# Power.net
KiCad netlist of a schematic drawn in Altium Designer
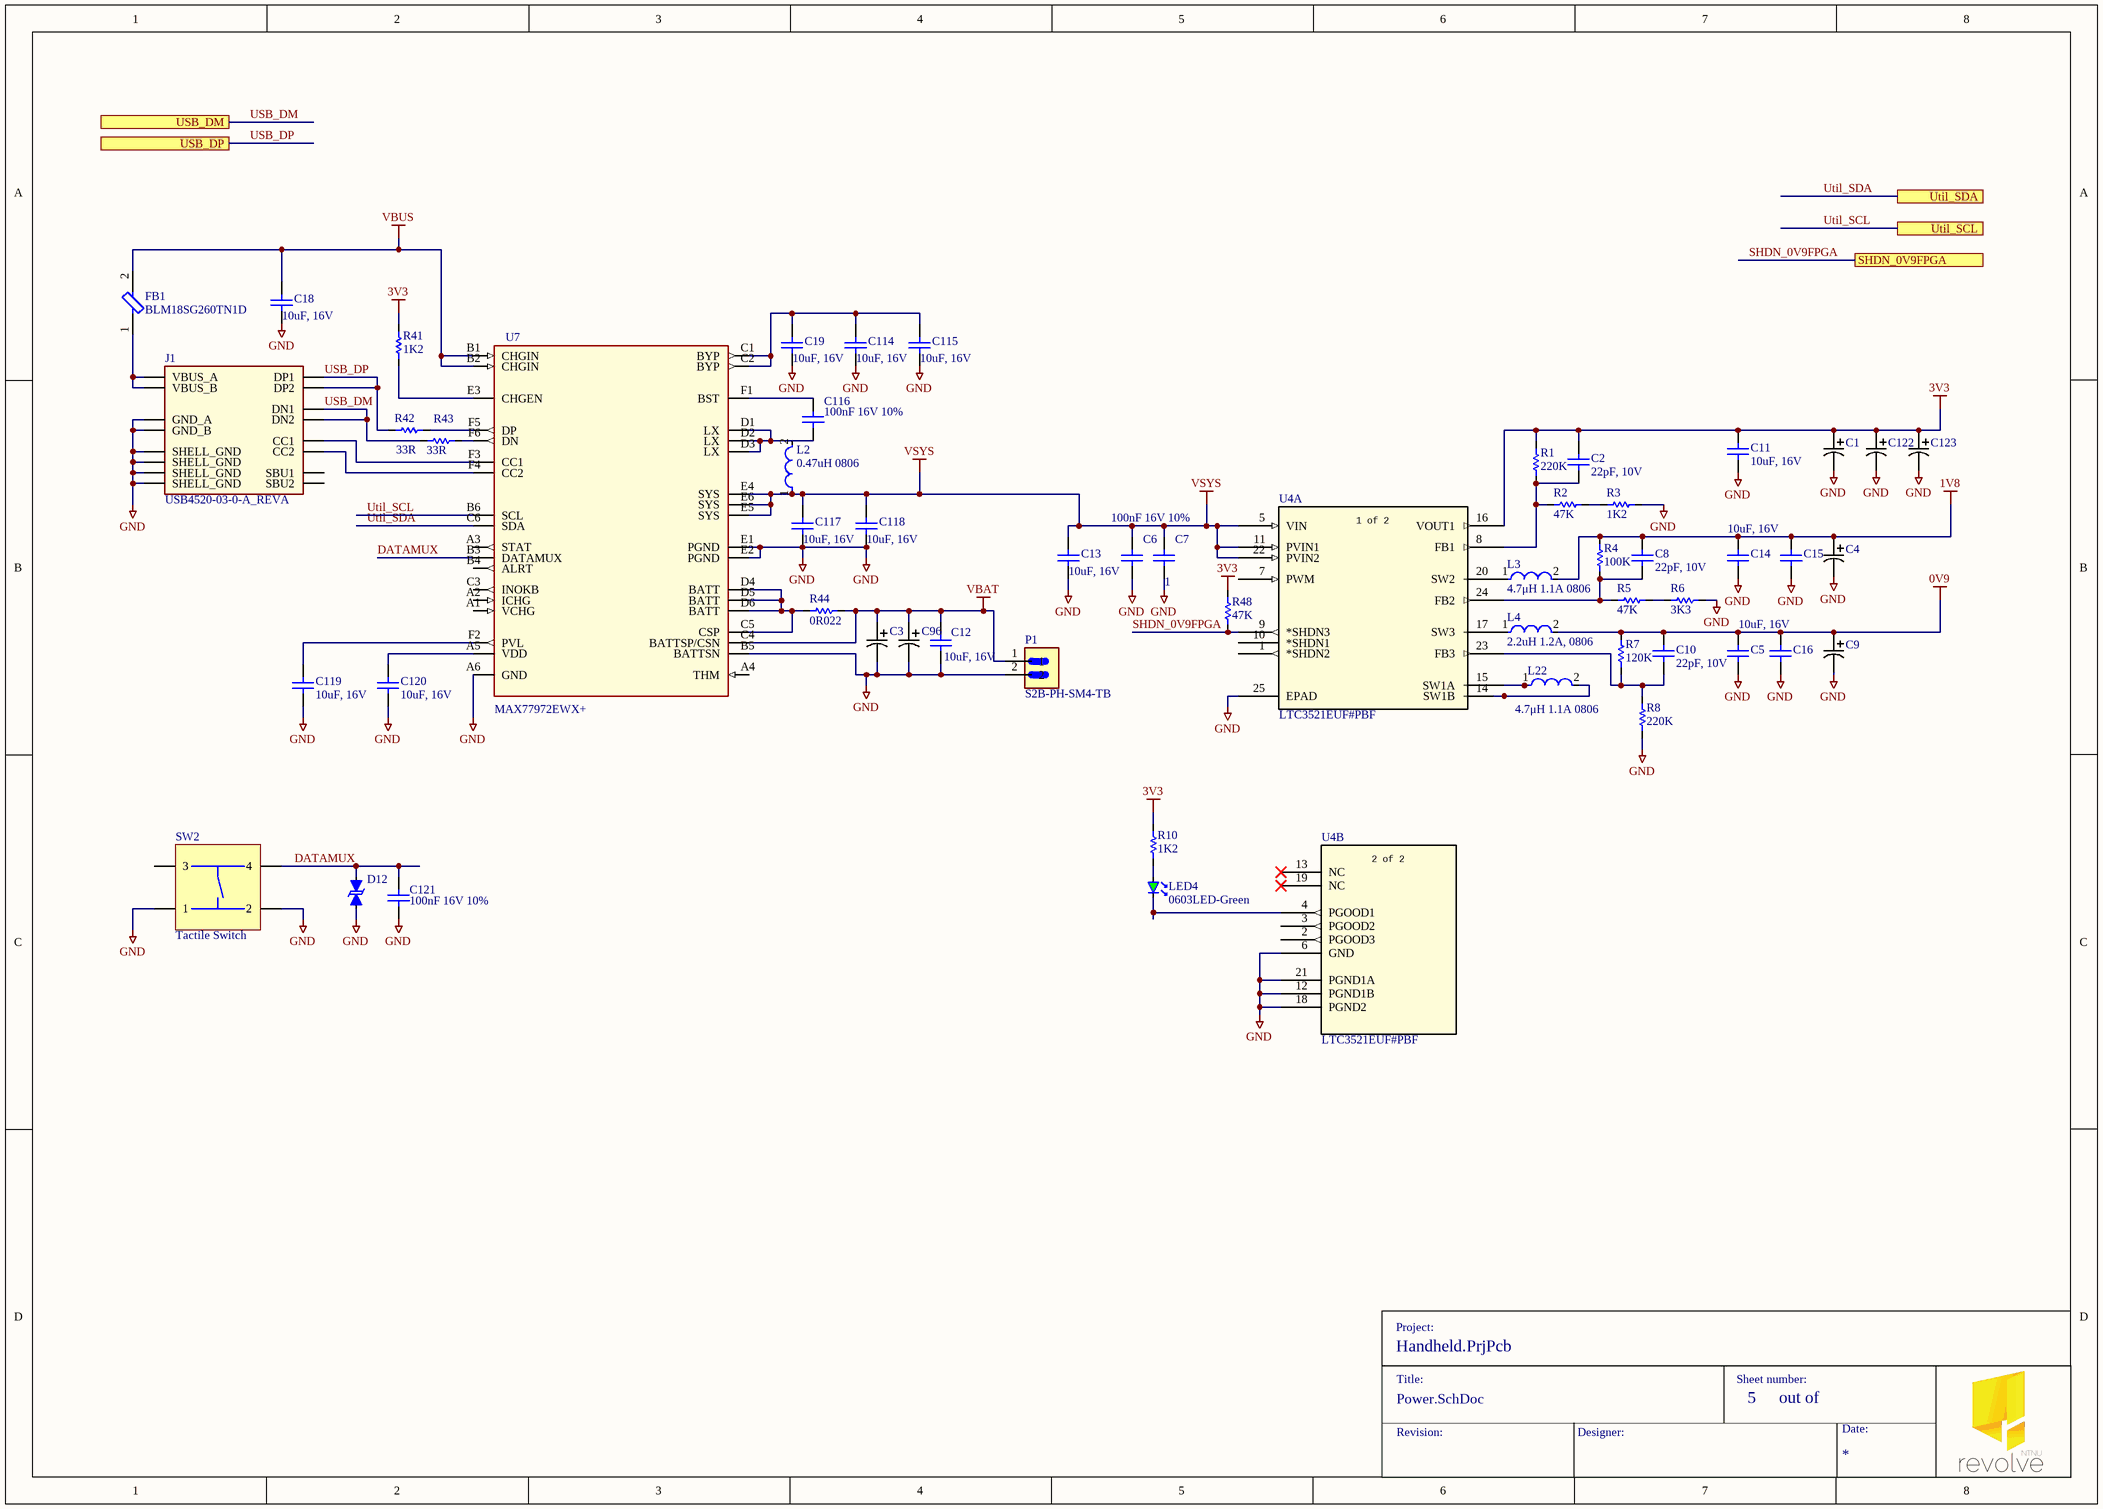
[diagram p0: Power.SchDoc]

(export (version "E")
  (design (tool "Eeschema 10.0.6"))
  (components
    (comp (ref "C1")
      (value "T529P476M006AAE150")
      (footprint "CAPMP2.1X1.25_1N_KEM")
      (fields (field (name "COPYRIGHT") "Copyright (C) 2025 Ultra Librarian. All rights reserved."))
      (libsource (lib "Handheld") (part "CAP-47uF-6.3V 0805"))
    )
    (comp (ref "C2")
      (value "22pF, 10V")
      (footprint "0603 Capacitor")
      (description "22pF, 10V, 1%, NP0, 0603")
      (libsource (lib "Revolve NTNU") (part "CAP"))
    )
    (comp (ref "C3")
      (value "T529P476M006AAE150")
      (footprint "CAPMP2.1X1.25_1N_KEM")
      (fields (field (name "COPYRIGHT") "Copyright (C) 2025 Ultra Librarian. All rights reserved."))
      (libsource (lib "Handheld") (part "CAP-47uF-6.3V 0805"))
    )
    (comp (ref "C4")
      (value "T529P476M006AAE150")
      (footprint "CAPMP2.1X1.25_1N_KEM")
      (fields (field (name "COPYRIGHT") "Copyright (C) 2025 Ultra Librarian. All rights reserved."))
      (libsource (lib "Handheld") (part "CAP-47uF-6.3V 0805"))
    )
    (comp (ref "C5")
      (value "10uF, 16V")
      (footprint "0603 Capacitor")
      (description "10uF, 16V, 20%, X5R, 0603")
      (libsource (lib "Revolve NTNU") (part "CAP"))
    )
    (comp (ref "C6")
      (value "100nF 16V 10%")
      (footprint "0402")
      (description "100nF 16V")
      (libsource (lib "Revolve NTNU") (part "CAP"))
    )
    (comp (ref "C7")
      (value "1")
      (footprint "0402")
      (description "100nF 16V")
      (libsource (lib "Revolve NTNU") (part "CAP"))
    )
    (comp (ref "C8")
      (value "22pF, 10V")
      (footprint "0603 Capacitor")
      (description "22pF, 10V, 1%, NP0, 0603")
      (libsource (lib "Revolve NTNU") (part "CAP"))
    )
    (comp (ref "C9")
      (value "T529P476M006AAE150")
      (footprint "CAPMP2.1X1.25_1N_KEM")
      (fields (field (name "COPYRIGHT") "Copyright (C) 2025 Ultra Librarian. All rights reserved."))
      (libsource (lib "Handheld") (part "CAP-47uF-6.3V 0805"))
    )
    (comp (ref "C10")
      (value "22pF, 10V")
      (footprint "0603 Capacitor")
      (description "22pF, 10V, 1%, NP0, 0603")
      (libsource (lib "Revolve NTNU") (part "CAP"))
    )
    (comp (ref "C11")
      (value "10uF, 16V")
      (footprint "0603 Capacitor")
      (description "10uF, 16V, 20%, X5R, 0603")
      (libsource (lib "Revolve NTNU") (part "CAP"))
    )
    (comp (ref "C12")
      (value "10uF, 16V")
      (footprint "0603 Capacitor")
      (description "10uF, 16V, 20%, X5R, 0603")
      (libsource (lib "Revolve NTNU") (part "CAP"))
    )
    (comp (ref "C13")
      (value "10uF, 16V")
      (footprint "0603 Capacitor")
      (description "10uF, 16V, 20%, X5R, 0603")
      (libsource (lib "Revolve NTNU") (part "CAP"))
    )
    (comp (ref "C14")
      (value "10uF, 16V")
      (footprint "0603 Capacitor")
      (description "10uF, 16V, 20%, X5R, 0603")
      (libsource (lib "Revolve NTNU") (part "CAP"))
    )
    (comp (ref "C15")
      (value "10uF, 16V")
      (footprint "0603 Capacitor")
      (description "10uF, 16V, 20%, X5R, 0603")
      (libsource (lib "Revolve NTNU") (part "CAP"))
    )
    (comp (ref "C16")
      (value "10uF, 16V")
      (footprint "0603 Capacitor")
      (description "10uF, 16V, 20%, X5R, 0603")
      (libsource (lib "Revolve NTNU") (part "CAP"))
    )
    (comp (ref "C18")
      (value "10uF, 16V")
      (footprint "0603 Capacitor")
      (description "10uF, 16V, 20%, X5R, 0603")
      (libsource (lib "Revolve NTNU") (part "CAP"))
    )
    (comp (ref "C19")
      (value "10uF, 16V")
      (footprint "0603 Capacitor")
      (description "10uF, 16V, 20%, X5R, 0603")
      (libsource (lib "Revolve NTNU") (part "CAP"))
    )
    (comp (ref "C96")
      (value "T529P476M006AAE150")
      (footprint "CAPMP2.1X1.25_1N_KEM")
      (fields (field (name "COPYRIGHT") "Copyright (C) 2025 Ultra Librarian. All rights reserved."))
      (libsource (lib "Handheld") (part "CAP-47uF-6.3V 0805"))
    )
    (comp (ref "C114")
      (value "10uF, 16V")
      (footprint "0603 Capacitor")
      (description "10uF, 16V, 20%, X5R, 0603")
      (libsource (lib "Revolve NTNU") (part "CAP"))
    )
    (comp (ref "C115")
      (value "10uF, 16V")
      (footprint "0603 Capacitor")
      (description "10uF, 16V, 20%, X5R, 0603")
      (libsource (lib "Revolve NTNU") (part "CAP"))
    )
    (comp (ref "C116")
      (value "100nF 16V 10%")
      (footprint "0402")
      (description "100nF 16V")
      (libsource (lib "Revolve NTNU") (part "CAP"))
    )
    (comp (ref "C117")
      (value "10uF, 16V")
      (footprint "0603 Capacitor")
      (description "10uF, 16V, 20%, X5R, 0603")
      (libsource (lib "Revolve NTNU") (part "CAP"))
    )
    (comp (ref "C118")
      (value "10uF, 16V")
      (footprint "0603 Capacitor")
      (description "10uF, 16V, 20%, X5R, 0603")
      (libsource (lib "Revolve NTNU") (part "CAP"))
    )
    (comp (ref "C119")
      (value "10uF, 16V")
      (footprint "0603 Capacitor")
      (description "10uF, 16V, 20%, X5R, 0603")
      (libsource (lib "Revolve NTNU") (part "CAP"))
    )
    (comp (ref "C120")
      (value "10uF, 16V")
      (footprint "0603 Capacitor")
      (description "10uF, 16V, 20%, X5R, 0603")
      (libsource (lib "Revolve NTNU") (part "CAP"))
    )
    (comp (ref "C121")
      (value "100nF 16V 10%")
      (footprint "0402")
      (description "100nF 16V")
      (libsource (lib "Revolve NTNU") (part "CAP"))
    )
    (comp (ref "C122")
      (value "T529P476M006AAE150")
      (footprint "CAPMP2.1X1.25_1N_KEM")
      (fields (field (name "COPYRIGHT") "Copyright (C) 2025 Ultra Librarian. All rights reserved."))
      (libsource (lib "Handheld") (part "CAP-47uF-6.3V 0805"))
    )
    (comp (ref "C123")
      (value "T529P476M006AAE150")
      (footprint "CAPMP2.1X1.25_1N_KEM")
      (fields (field (name "COPYRIGHT") "Copyright (C) 2025 Ultra Librarian. All rights reserved."))
      (libsource (lib "Handheld") (part "CAP-47uF-6.3V 0805"))
    )
    (comp (ref "D12")
      (value "DESD3V3E1BL-7B")
      (footprint "CR_X1-DFN1006-2_DIO-M")
      (description "TVS DIODE 3.3V, DFN1006-2, 13pF @ 1MHz")
      (fields (field (name "COPYRIGHT") "Copyright (C) 2025 Ultra Librarian. All rights reserved."))
      (libsource (lib "Handheld") (part "DESD3V3E1BL-7B"))
    )
    (comp (ref "FB1")
      (value "BLM18SG260TN1D")
      (footprint "FP-BLM18-0_15-t0_5-d3_3-IPC_B")
      (description "Ferrite Bead, 26 Ohm @ 100 MHz, 6A, 7mOhm")
      (libsource (lib "Revolve NTNU") (part "5f30dd21d616792df468990f7003faa"))
    )
    (comp (ref "J1")
      (value "USB4520-03-0-A_REVA")
      (footprint "GCT_USB4520-03-0-A_REVA")
      (description "USB Type C Receptacle for USB 2.0, SMT Type Mid Mount, 2.0mm Offset")
      (fields (field (name "MF") "Global Connector Technology") (field (name "MP") "USB4520-03-0-A"))
      (libsource (lib "Handheld") (part "USB-C"))
    )
    (comp (ref "L2")
      (value "0.47uH 0806")
      (footprint "FP-LQM2MPN_G0-IPC_B")
      (fields (field (name "TOLERANCE") "30%"))
      (libsource (lib "Handheld") (part "Inductor SMD 0.47uH"))
    )
    (comp (ref "L3")
      (value "4.7μH 1.1A 0806")
      (footprint "FP-LQM2MPN_G0-IPC_B")
      (description "Multilayer Type Inductor for Power Lines, 0806 (2016), 4.7μH, 30%, 0.175Ω, 1.1A, LQM2MPN4R7NG0L")
      (fields (field (name "TOLERANCE") "30%"))
      (libsource (lib "Handheld") (part "Inductor SMD 4.7uH 1.1A"))
    )
    (comp (ref "L4")
      (value "2.2uH 1.2A, 0806")
      (footprint "FP-LQM2MPN_G0-IPC_B")
      (description "Multilayer Type Inductor for Power Lines, 0806 (2016), 4.7μH, 30%, 0.175Ω, 1.1A, LQM2MPN2R2NG0L")
      (fields (field (name "TOLERANCE") "30%"))
      (libsource (lib "Handheld") (part "Inductor SMD 2.2uH 1.2A"))
    )
    (comp (ref "L22")
      (value "4.7μH 1.1A 0806")
      (footprint "FP-LQM2MPN_G0-IPC_B")
      (description "Multilayer Type Inductor for Power Lines, 0806 (2016), 4.7μH, 30%, 0.175Ω, 1.1A, LQM2MPN4R7NG0L")
      (fields (field (name "TOLERANCE") "30%"))
      (libsource (lib "Handheld") (part "Inductor SMD 4.7uH 1.1A"))
    )
    (comp (ref "LED4")
      (value "0603LED-Green")
      (footprint "LED-0603-RED")
      (description "SMD LED 0603, Green")
      (libsource (lib "Revolve NTNU") (part "LED"))
    )
    (comp (ref "P1")
      (value "S2B-PH-SM4-TB")
      (footprint "JST_S2B-PH-SM4-TB")
      (description "Connector Header Surface Mount, Right Angle 2 position 0.079 (2.00mm)")
      (fields (field (name "MF") "JST Sales"))
      (libsource (lib "Eirik Silnes") (part "S2B-PH-SM4-TB"))
    )
    (comp (ref "R1")
      (value "220K")
      (footprint "0603 Resistor")
      (description "220K, 1%, 1/10W, 0603")
      (libsource (lib "Revolve NTNU") (part "Resistor"))
    )
    (comp (ref "R2")
      (value "47K")
      (footprint "0603 Resistor")
      (description "47K, 1%, 1/10W, 0603")
      (libsource (lib "Revolve NTNU") (part "Resistor"))
    )
    (comp (ref "R3")
      (value "1K2")
      (footprint "0603 Resistor")
      (description "1K2, 5%, 1/10W, 0603")
      (libsource (lib "Revolve NTNU") (part "Resistor"))
    )
    (comp (ref "R4")
      (value "100K")
      (footprint "0603 Resistor")
      (description "100K, 1%, 1/10W, 0603")
      (fields (field (name "TOLERANCE") "1%") (field (name "MANUFACTURER PART NUMBER") "ERJ-3EKF1003V"))
      (libsource (lib "Revolve NTNU") (part "Resistor"))
    )
    (comp (ref "R5")
      (value "47K")
      (footprint "0603 Resistor")
      (description "47K, 1%, 1/10W, 0603")
      (libsource (lib "Revolve NTNU") (part "Resistor"))
    )
    (comp (ref "R6")
      (value "3K3")
      (footprint "0603 Resistor")
      (description "3K3, 5%, 1/10W, 0603")
      (libsource (lib "Revolve NTNU") (part "Resistor"))
    )
    (comp (ref "R7")
      (value "120K")
      (footprint "0603 Resistor")
      (description "120K, 0.1%, 1/10W, 0603")
      (libsource (lib "Revolve NTNU") (part "Resistor"))
    )
    (comp (ref "R8")
      (value "220K")
      (footprint "0603 Resistor")
      (description "220K, 1%, 1/10W, 0603")
      (libsource (lib "Revolve NTNU") (part "Resistor"))
    )
    (comp (ref "R10")
      (value "1K2")
      (footprint "0603 Resistor")
      (description "1K2, 5%, 1/10W, 0603")
      (libsource (lib "Revolve NTNU") (part "Resistor"))
    )
    (comp (ref "R41")
      (value "1K2")
      (footprint "0603 Resistor")
      (description "1K2, 5%, 1/10W, 0603")
      (libsource (lib "Revolve NTNU") (part "Resistor"))
    )
    (comp (ref "R42")
      (value "33R")
      (footprint "0603 Resistor")
      (description "33R, 1%, 1/10W, 0603")
      (fields (field (name "TOLERANCE") "1%") (field (name "MANUFACTURER") "Panasonic"))
      (libsource (lib "Revolve NTNU") (part "Resistor"))
    )
    (comp (ref "R43")
      (value "33R")
      (footprint "0603 Resistor")
      (description "33R, 1%, 1/10W, 0603")
      (fields (field (name "TOLERANCE") "1%") (field (name "MANUFACTURER") "Panasonic"))
      (libsource (lib "Revolve NTNU") (part "Resistor"))
    )
    (comp (ref "R44")
      (value "0R022")
      (footprint "1206 Resistor Package")
      (description "0R022, 2%, 1/2W, 1206")
      (libsource (lib "Revolve NTNU") (part "Resistor"))
    )
    (comp (ref "R48")
      (value "47K")
      (footprint "0603 Resistor")
      (description "47K, 1%, 1/10W, 0603")
      (libsource (lib "Revolve NTNU") (part "Resistor"))
    )
    (comp (ref "SW2")
      (value "Tactile Switch")
      (footprint "TE connectivity part no. 2-1437565-8")
      (description "Tactile Switch, 24V, 50 mA, Pushbutton - N.O, 2-1437565-8")
      (libsource (lib "Revolve NTNU") (part "Component_1"))
    )
    (comp (ref "U4")
      (value "LTC3521EUF#PBF")
      (footprint "QFN-24_UF_LIT-M")
      (description "1A Buck-Boost DC/DC and Dual 600mA Buck DC/DC Converters")
      (fields (field (name "COPYRIGHT") "Copyright (C) 2025 Ultra Librarian. All rights reserved."))
      (libsource (lib "Handheld") (part "LTC3521EUFPBF"))
    )
    (comp (ref "U7")
      (value "MAX77972EWX+")
      (footprint "21-100517_W363B3+1_ADI")
      (description "AccuCharge + ModelGauge 1-Cell Fuel Gauge and 3A Charger with Integrated USB Type-C Detection")
      (fields (field (name "COPYRIGHT") "Copyright (C) 2025 Ultra Librarian. All rights reserved."))
      (libsource (lib "Handheld") (part "MAX77972EWX+"))
    )
  )
  (nets
    (net (code "1") (name "/DATAMUX") (class "Default")
      (node (ref "C121") (pin "2") (pinfunction "2_2") (pintype "passive"))
      (node (ref "D12") (pin "1") (pinfunction "CATHODE_1") (pintype "passive"))
      (node (ref "SW2") (pin "4") (pinfunction "4_4") (pintype "passive"))
      (node (ref "U7") (pin "B3") (pinfunction "DATAMUX_B3") (pintype "passive"))
    )
    (net (code "2") (name "/SHDN_0V9FPGA") (class "Default")
      (node (ref "R48") (pin "1") (pinfunction "1_1") (pintype "passive"))
      (node (ref "U4") (pin "9") (pinfunction "*SHDN3_9") (pintype "output"))
    )
    (net (code "3") (name "/USB_DM") (class "Default")
      (node (ref "J1") (pin "A7") (pinfunction "DN1_A7") (pintype "passive"))
      (node (ref "J1") (pin "B7") (pinfunction "DN2_B7") (pintype "passive"))
      (node (ref "R43") (pin "1") (pinfunction "1_1") (pintype "passive"))
    )
    (net (code "4") (name "/USB_DP") (class "Default")
      (node (ref "J1") (pin "A6") (pinfunction "DP1_A6") (pintype "passive"))
      (node (ref "J1") (pin "B6") (pinfunction "DP2_B6") (pintype "passive"))
      (node (ref "R42") (pin "1") (pinfunction "1_1") (pintype "passive"))
    )
    (net (code "5") (name "/Util_SCL") (class "Default")
      (node (ref "U7") (pin "B6") (pinfunction "SCL_B6") (pintype "passive"))
    )
    (net (code "6") (name "/Util_SDA") (class "Default")
      (node (ref "U7") (pin "C6") (pinfunction "SDA_C6") (pintype "passive"))
    )
    (net (code "7") (name "0V9") (class "Default")
      (node (ref "C10") (pin "2") (pinfunction "2_2") (pintype "passive"))
      (node (ref "C16") (pin "2") (pinfunction "2_2") (pintype "passive"))
      (node (ref "C5") (pin "2") (pinfunction "2_2") (pintype "passive"))
      (node (ref "C9") (pin "1") (pinfunction "1_1") (pintype "passive"))
      (node (ref "L4") (pin "2") (pinfunction "2_2") (pintype "passive"))
      (node (ref "R7") (pin "2") (pinfunction "2_2") (pintype "passive"))
    )
    (net (code "8") (name "1V8") (class "Default")
      (node (ref "C14") (pin "2") (pinfunction "2_2") (pintype "passive"))
      (node (ref "C15") (pin "2") (pinfunction "2_2") (pintype "passive"))
      (node (ref "C4") (pin "1") (pinfunction "1_1") (pintype "passive"))
      (node (ref "C8") (pin "2") (pinfunction "2_2") (pintype "passive"))
      (node (ref "L3") (pin "2") (pinfunction "2_2") (pintype "passive"))
      (node (ref "R4") (pin "2") (pinfunction "2_2") (pintype "passive"))
    )
    (net (code "9") (name "3V3") (class "Default")
      (node (ref "C1") (pin "1") (pinfunction "1_1") (pintype "passive"))
      (node (ref "C11") (pin "2") (pinfunction "2_2") (pintype "passive"))
      (node (ref "C122") (pin "1") (pinfunction "1_1") (pintype "passive"))
      (node (ref "C123") (pin "1") (pinfunction "1_1") (pintype "passive"))
      (node (ref "C2") (pin "2") (pinfunction "2_2") (pintype "passive"))
      (node (ref "R1") (pin "2") (pinfunction "2_2") (pintype "passive"))
      (node (ref "R10") (pin "2") (pinfunction "2_2") (pintype "passive"))
      (node (ref "R41") (pin "2") (pinfunction "2_2") (pintype "passive"))
      (node (ref "R48") (pin "2") (pinfunction "2_2") (pintype "passive"))
      (node (ref "U4") (pin "16") (pinfunction "VOUT1_16") (pintype "output"))
    )
    (net (code "10") (name "GND") (class "Default")
      (node (ref "C1") (pin "2") (pinfunction "2_2") (pintype "passive"))
      (node (ref "C11") (pin "1") (pinfunction "1_1") (pintype "passive"))
      (node (ref "C114") (pin "1") (pinfunction "1_1") (pintype "passive"))
      (node (ref "C115") (pin "1") (pinfunction "1_1") (pintype "passive"))
      (node (ref "C117") (pin "1") (pinfunction "1_1") (pintype "passive"))
      (node (ref "C118") (pin "1") (pinfunction "1_1") (pintype "passive"))
      (node (ref "C119") (pin "1") (pinfunction "1_1") (pintype "passive"))
      (node (ref "C12") (pin "1") (pinfunction "1_1") (pintype "passive"))
      (node (ref "C120") (pin "1") (pinfunction "1_1") (pintype "passive"))
      (node (ref "C121") (pin "1") (pinfunction "1_1") (pintype "passive"))
      (node (ref "C122") (pin "2") (pinfunction "2_2") (pintype "passive"))
      (node (ref "C123") (pin "2") (pinfunction "2_2") (pintype "passive"))
      (node (ref "C13") (pin "1") (pinfunction "1_1") (pintype "passive"))
      (node (ref "C14") (pin "1") (pinfunction "1_1") (pintype "passive"))
      (node (ref "C15") (pin "1") (pinfunction "1_1") (pintype "passive"))
      (node (ref "C16") (pin "1") (pinfunction "1_1") (pintype "passive"))
      (node (ref "C18") (pin "1") (pinfunction "1_1") (pintype "passive"))
      (node (ref "C19") (pin "1") (pinfunction "1_1") (pintype "passive"))
      (node (ref "C3") (pin "2") (pinfunction "2_2") (pintype "passive"))
      (node (ref "C4") (pin "2") (pinfunction "2_2") (pintype "passive"))
      (node (ref "C5") (pin "1") (pinfunction "1_1") (pintype "passive"))
      (node (ref "C6") (pin "1") (pinfunction "1_1") (pintype "passive"))
      (node (ref "C7") (pin "1") (pinfunction "1_1") (pintype "passive"))
      (node (ref "C9") (pin "2") (pinfunction "2_2") (pintype "passive"))
      (node (ref "C96") (pin "2") (pinfunction "2_2") (pintype "passive"))
      (node (ref "D12") (pin "2") (pinfunction "ANODE_2") (pintype "passive"))
      (node (ref "J1") (pin "A1_B12") (pinfunction "GND_A_A1_B12") (pintype "power_in"))
      (node (ref "J1") (pin "B1_A12") (pinfunction "GND_B_B1_A12") (pintype "power_in"))
      (node (ref "J1") (pin "S1") (pinfunction "SHELL_GND_S1") (pintype "power_in"))
      (node (ref "J1") (pin "S2") (pinfunction "SHELL_GND_S2") (pintype "power_in"))
      (node (ref "J1") (pin "S3") (pinfunction "SHELL_GND_S3") (pintype "power_in"))
      (node (ref "J1") (pin "S4") (pinfunction "SHELL_GND_S4") (pintype "power_in"))
      (node (ref "P1") (pin "2") (pinfunction "2_2") (pintype "passive"))
      (node (ref "R3") (pin "2") (pinfunction "2_2") (pintype "passive"))
      (node (ref "R6") (pin "2") (pinfunction "2_2") (pintype "passive"))
      (node (ref "R8") (pin "1") (pinfunction "1_1") (pintype "passive"))
      (node (ref "SW2") (pin "1") (pinfunction "1_1") (pintype "passive"))
      (node (ref "SW2") (pin "2") (pinfunction "2_2") (pintype "passive"))
      (node (ref "U4") (pin "12") (pinfunction "PGND1B_12") (pintype "power_in"))
      (node (ref "U4") (pin "18") (pinfunction "PGND2_18") (pintype "power_in"))
      (node (ref "U4") (pin "21") (pinfunction "PGND1A_21") (pintype "power_in"))
      (node (ref "U4") (pin "25") (pinfunction "EPAD_25") (pintype "passive"))
      (node (ref "U4") (pin "6") (pinfunction "GND_6") (pintype "power_in"))
      (node (ref "U7") (pin "A6") (pinfunction "GND_A6") (pintype "power_in"))
      (node (ref "U7") (pin "B5") (pinfunction "BATTSN_B5") (pintype "passive"))
      (node (ref "U7") (pin "E1") (pinfunction "PGND_E1") (pintype "power_in"))
      (node (ref "U7") (pin "E2") (pinfunction "PGND_E2") (pintype "power_in"))
    )
    (net (code "11") (name "Net-(C114-Pad2)") (class "Default")
      (node (ref "C114") (pin "2") (pinfunction "2_2") (pintype "passive"))
      (node (ref "C115") (pin "2") (pinfunction "2_2") (pintype "passive"))
      (node (ref "C19") (pin "2") (pinfunction "2_2") (pintype "passive"))
      (node (ref "U7") (pin "C1") (pinfunction "BYP_C1") (pintype "output"))
      (node (ref "U7") (pin "C2") (pinfunction "BYP_C2") (pintype "output"))
    )
    (net (code "12") (name "Net-(C116-Pad1)") (class "Default")
      (node (ref "C116") (pin "1") (pinfunction "1_1") (pintype "passive"))
      (node (ref "U7") (pin "D1") (pinfunction "LX_D1") (pintype "passive"))
      (node (ref "U7") (pin "D2") (pinfunction "LX_D2") (pintype "passive"))
      (node (ref "U7") (pin "D3") (pinfunction "LX_D3") (pintype "passive"))
    )
    (net (code "13") (name "Net-(J1-CC1)") (class "Default")
      (node (ref "J1") (pin "A5") (pinfunction "CC1_A5") (pintype "passive"))
      (node (ref "U7") (pin "F3") (pinfunction "CC1_F3") (pintype "passive"))
    )
    (net (code "14") (name "Net-(J1-CC2)") (class "Default")
      (node (ref "J1") (pin "B5") (pinfunction "CC2_B5") (pintype "passive"))
      (node (ref "U7") (pin "F4") (pinfunction "CC2_F4") (pintype "passive"))
    )
    (net (code "15") (name "Net-(J1-VBUS_A)") (class "Default")
      (node (ref "FB1") (pin "1") (pinfunction "1_1") (pintype "passive"))
      (node (ref "J1") (pin "A4_B9") (pinfunction "VBUS_A_A4_B9") (pintype "power_in"))
      (node (ref "J1") (pin "B4_A9") (pinfunction "VBUS_B_B4_A9") (pintype "power_in"))
    )
    (net (code "16") (name "Net-(LED4-A)") (class "Default")
      (node (ref "LED4") (pin "1") (pinfunction "A_1") (pintype "passive"))
      (node (ref "R10") (pin "1") (pinfunction "1_1") (pintype "passive"))
    )
    (net (code "17") (name "Net-(LED4-K)") (class "Default")
      (node (ref "LED4") (pin "2") (pinfunction "K_2") (pintype "passive"))
      (node (ref "U4") (pin "4") (pinfunction "PGOOD1_4") (pintype "output"))
    )
    (net (code "18") (name "Net-(R2-Pad1)") (class "Default")
      (node (ref "R2") (pin "1") (pinfunction "1_1") (pintype "passive"))
      (node (ref "R3") (pin "1") (pinfunction "1_1") (pintype "passive"))
    )
    (net (code "19") (name "Net-(R5-Pad2)") (class "Default")
      (node (ref "R5") (pin "2") (pinfunction "2_2") (pintype "passive"))
      (node (ref "R6") (pin "1") (pinfunction "1_1") (pintype "passive"))
    )
    (net (code "20") (name "Net-(U4A-FB1)") (class "Default")
      (node (ref "C2") (pin "1") (pinfunction "1_1") (pintype "passive"))
      (node (ref "R1") (pin "1") (pinfunction "1_1") (pintype "passive"))
      (node (ref "R2") (pin "2") (pinfunction "2_2") (pintype "passive"))
      (node (ref "U4") (pin "8") (pinfunction "FB1_8") (pintype "output"))
    )
    (net (code "21") (name "Net-(U4A-FB2)") (class "Default")
      (node (ref "C8") (pin "1") (pinfunction "1_1") (pintype "passive"))
      (node (ref "R4") (pin "1") (pinfunction "1_1") (pintype "passive"))
      (node (ref "R5") (pin "1") (pinfunction "1_1") (pintype "passive"))
      (node (ref "U4") (pin "24") (pinfunction "FB2_24") (pintype "output"))
    )
    (net (code "22") (name "Net-(U4A-FB3)") (class "Default")
      (node (ref "C10") (pin "1") (pinfunction "1_1") (pintype "passive"))
      (node (ref "R7") (pin "1") (pinfunction "1_1") (pintype "passive"))
      (node (ref "R8") (pin "2") (pinfunction "2_2") (pintype "passive"))
      (node (ref "U4") (pin "23") (pinfunction "FB3_23") (pintype "output"))
    )
    (net (code "23") (name "Net-(U4A-SW1A)") (class "Default")
      (node (ref "L22") (pin "1") (pinfunction "1_1") (pintype "passive"))
      (node (ref "U4") (pin "15") (pinfunction "SW1A_15") (pintype "passive"))
    )
    (net (code "24") (name "Net-(U4A-SW2)") (class "Default")
      (node (ref "L3") (pin "1") (pinfunction "1_1") (pintype "passive"))
      (node (ref "U4") (pin "20") (pinfunction "SW2_20") (pintype "passive"))
    )
    (net (code "25") (name "Net-(U4A-SW3)") (class "Default")
      (node (ref "L4") (pin "1") (pinfunction "1_1") (pintype "passive"))
      (node (ref "U4") (pin "17") (pinfunction "SW3_17") (pintype "passive"))
    )
    (net (code "26") (name "Net-(U7-BST)") (class "Default")
      (node (ref "C116") (pin "2") (pinfunction "2_2") (pintype "passive"))
      (node (ref "U7") (pin "F1") (pinfunction "BST_F1") (pintype "power_in"))
    )
    (net (code "27") (name "Net-(U7-CHGEN)") (class "Default")
      (node (ref "R41") (pin "1") (pinfunction "1_1") (pintype "passive"))
      (node (ref "U7") (pin "E3") (pinfunction "CHGEN_E3") (pintype "passive"))
    )
    (net (code "28") (name "Net-(U7-CSP)") (class "Default")
      (node (ref "R44") (pin "1") (pinfunction "1_1") (pintype "passive"))
      (node (ref "U7") (pin "C5") (pinfunction "CSP_C5") (pintype "passive"))
      (node (ref "U7") (pin "D4") (pinfunction "BATT_D4") (pintype "power_in"))
      (node (ref "U7") (pin "D5") (pinfunction "BATT_D5") (pintype "power_in"))
      (node (ref "U7") (pin "D6") (pinfunction "BATT_D6") (pintype "power_in"))
    )
    (net (code "29") (name "Net-(U7-DN)") (class "Default")
      (node (ref "R43") (pin "2") (pinfunction "2_2") (pintype "passive"))
      (node (ref "U7") (pin "F6") (pinfunction "DN_F6") (pintype "output"))
    )
    (net (code "30") (name "Net-(U7-DP)") (class "Default")
      (node (ref "R42") (pin "2") (pinfunction "2_2") (pintype "passive"))
      (node (ref "U7") (pin "F5") (pinfunction "DP_F5") (pintype "output"))
    )
    (net (code "31") (name "Net-(U7-PVL)") (class "Default")
      (node (ref "C119") (pin "2") (pinfunction "2_2") (pintype "passive"))
      (node (ref "U7") (pin "F2") (pinfunction "PVL_F2") (pintype "output"))
    )
    (net (code "32") (name "Net-(U7-VDD)") (class "Default")
      (node (ref "C120") (pin "2") (pinfunction "2_2") (pintype "passive"))
      (node (ref "U7") (pin "A5") (pinfunction "VDD_A5") (pintype "power_in"))
    )
    (net (code "33") (name "VBAT") (class "Default")
      (node (ref "C12") (pin "2") (pinfunction "2_2") (pintype "passive"))
      (node (ref "C3") (pin "1") (pinfunction "1_1") (pintype "passive"))
      (node (ref "C96") (pin "1") (pinfunction "1_1") (pintype "passive"))
      (node (ref "P1") (pin "1") (pinfunction "1_1") (pintype "passive"))
      (node (ref "R44") (pin "2") (pinfunction "2_2") (pintype "passive"))
      (node (ref "U7") (pin "C4") (pinfunction "BATTSP/CSN_C4") (pintype "passive"))
    )
    (net (code "34") (name "VBUS") (class "Default")
      (node (ref "C18") (pin "2") (pinfunction "2_2") (pintype "passive"))
      (node (ref "FB1") (pin "2") (pinfunction "2_2") (pintype "passive"))
      (node (ref "U7") (pin "B1") (pinfunction "CHGIN_B1") (pintype "input"))
      (node (ref "U7") (pin "B2") (pinfunction "CHGIN_B2") (pintype "input"))
    )
    (net (code "35") (name "VSYS") (class "Default")
      (node (ref "C117") (pin "2") (pinfunction "2_2") (pintype "passive"))
      (node (ref "C118") (pin "2") (pinfunction "2_2") (pintype "passive"))
      (node (ref "C13") (pin "2") (pinfunction "2_2") (pintype "passive"))
      (node (ref "C6") (pin "2") (pinfunction "2_2") (pintype "passive"))
      (node (ref "C7") (pin "2") (pinfunction "2_2") (pintype "passive"))
      (node (ref "L2") (pin "1") (pinfunction "1_1") (pintype "passive"))
      (node (ref "U4") (pin "11") (pinfunction "PVIN1_11") (pintype "input"))
      (node (ref "U4") (pin "22") (pinfunction "PVIN2_22") (pintype "input"))
      (node (ref "U4") (pin "5") (pinfunction "VIN_5") (pintype "input"))
      (node (ref "U7") (pin "E4") (pinfunction "SYS_E4") (pintype "passive"))
      (node (ref "U7") (pin "E5") (pinfunction "SYS_E5") (pintype "passive"))
      (node (ref "U7") (pin "E6") (pinfunction "SYS_E6") (pintype "passive"))
    )
    (net (code "36") (name "unconnected-(J1-SBU1-PadA8)") (class "Default")
      (node (ref "J1") (pin "A8") (pinfunction "SBU1_A8") (pintype "passive"))
    )
    (net (code "37") (name "unconnected-(J1-SBU2-PadB8)") (class "Default")
      (node (ref "J1") (pin "B8") (pinfunction "SBU2_B8") (pintype "passive"))
    )
    (net (code "38") (name "unconnected-(L2-Pad2)") (class "Default")
      (node (ref "L2") (pin "2") (pinfunction "2_2") (pintype "passive"))
    )
    (net (code "39") (name "unconnected-(L22-Pad2)") (class "Default")
      (node (ref "L22") (pin "2") (pinfunction "2_2") (pintype "passive"))
    )
    (net (code "40") (name "unconnected-(SW2-Pad3)") (class "Default")
      (node (ref "SW2") (pin "3") (pinfunction "3_3") (pintype "passive"))
    )
    (net (code "41") (name "unconnected-(U4A-*SHDN1-Pad10)") (class "Default")
      (node (ref "U4") (pin "10") (pinfunction "*SHDN1_10") (pintype "passive"))
    )
    (net (code "42") (name "unconnected-(U4A-*SHDN2-Pad1)") (class "Default")
      (node (ref "U4") (pin "1") (pinfunction "*SHDN2_1") (pintype "output"))
    )
    (net (code "43") (name "unconnected-(U4A-PWM-Pad7)") (class "Default")
      (node (ref "U4") (pin "7") (pinfunction "PWM_7") (pintype "input"))
    )
    (net (code "44") (name "unconnected-(U4A-SW1B-Pad14)") (class "Default")
      (node (ref "U4") (pin "14") (pinfunction "SW1B_14") (pintype "passive"))
    )
    (net (code "45") (name "unconnected-(U4B-NC-Pad13)") (class "Default")
      (node (ref "U4") (pin "13") (pinfunction "NC_13") (pintype "passive+no_connect"))
    )
    (net (code "46") (name "unconnected-(U4B-NC-Pad19)") (class "Default")
      (node (ref "U4") (pin "19") (pinfunction "NC_19") (pintype "passive+no_connect"))
    )
    (net (code "47") (name "unconnected-(U4B-PGOOD2-Pad3)") (class "Default")
      (node (ref "U4") (pin "3") (pinfunction "PGOOD2_3") (pintype "output"))
    )
    (net (code "48") (name "unconnected-(U4B-PGOOD3-Pad2)") (class "Default")
      (node (ref "U4") (pin "2") (pinfunction "PGOOD3_2") (pintype "output"))
    )
    (net (code "49") (name "unconnected-(U7-ALRT-PadB4)") (class "Default")
      (node (ref "U7") (pin "B4") (pinfunction "ALRT_B4") (pintype "output"))
    )
    (net (code "50") (name "unconnected-(U7-ICHG-PadA2)") (class "Default")
      (node (ref "U7") (pin "A2") (pinfunction "ICHG_A2") (pintype "input"))
    )
    (net (code "51") (name "unconnected-(U7-INOKB-PadC3)") (class "Default")
      (node (ref "U7") (pin "C3") (pinfunction "INOKB_C3") (pintype "output"))
    )
    (net (code "52") (name "unconnected-(U7-STAT-PadA3)") (class "Default")
      (node (ref "U7") (pin "A3") (pinfunction "STAT_A3") (pintype "output"))
    )
    (net (code "53") (name "unconnected-(U7-THM-PadA4)") (class "Default")
      (node (ref "U7") (pin "A4") (pinfunction "THM_A4") (pintype "input"))
    )
    (net (code "54") (name "unconnected-(U7-VCHG-PadA1)") (class "Default")
      (node (ref "U7") (pin "A1") (pinfunction "VCHG_A1") (pintype "input"))
    )
  )
)
